# cpu_board.net
KiCad netlist of a schematic drawn in Altium Designer
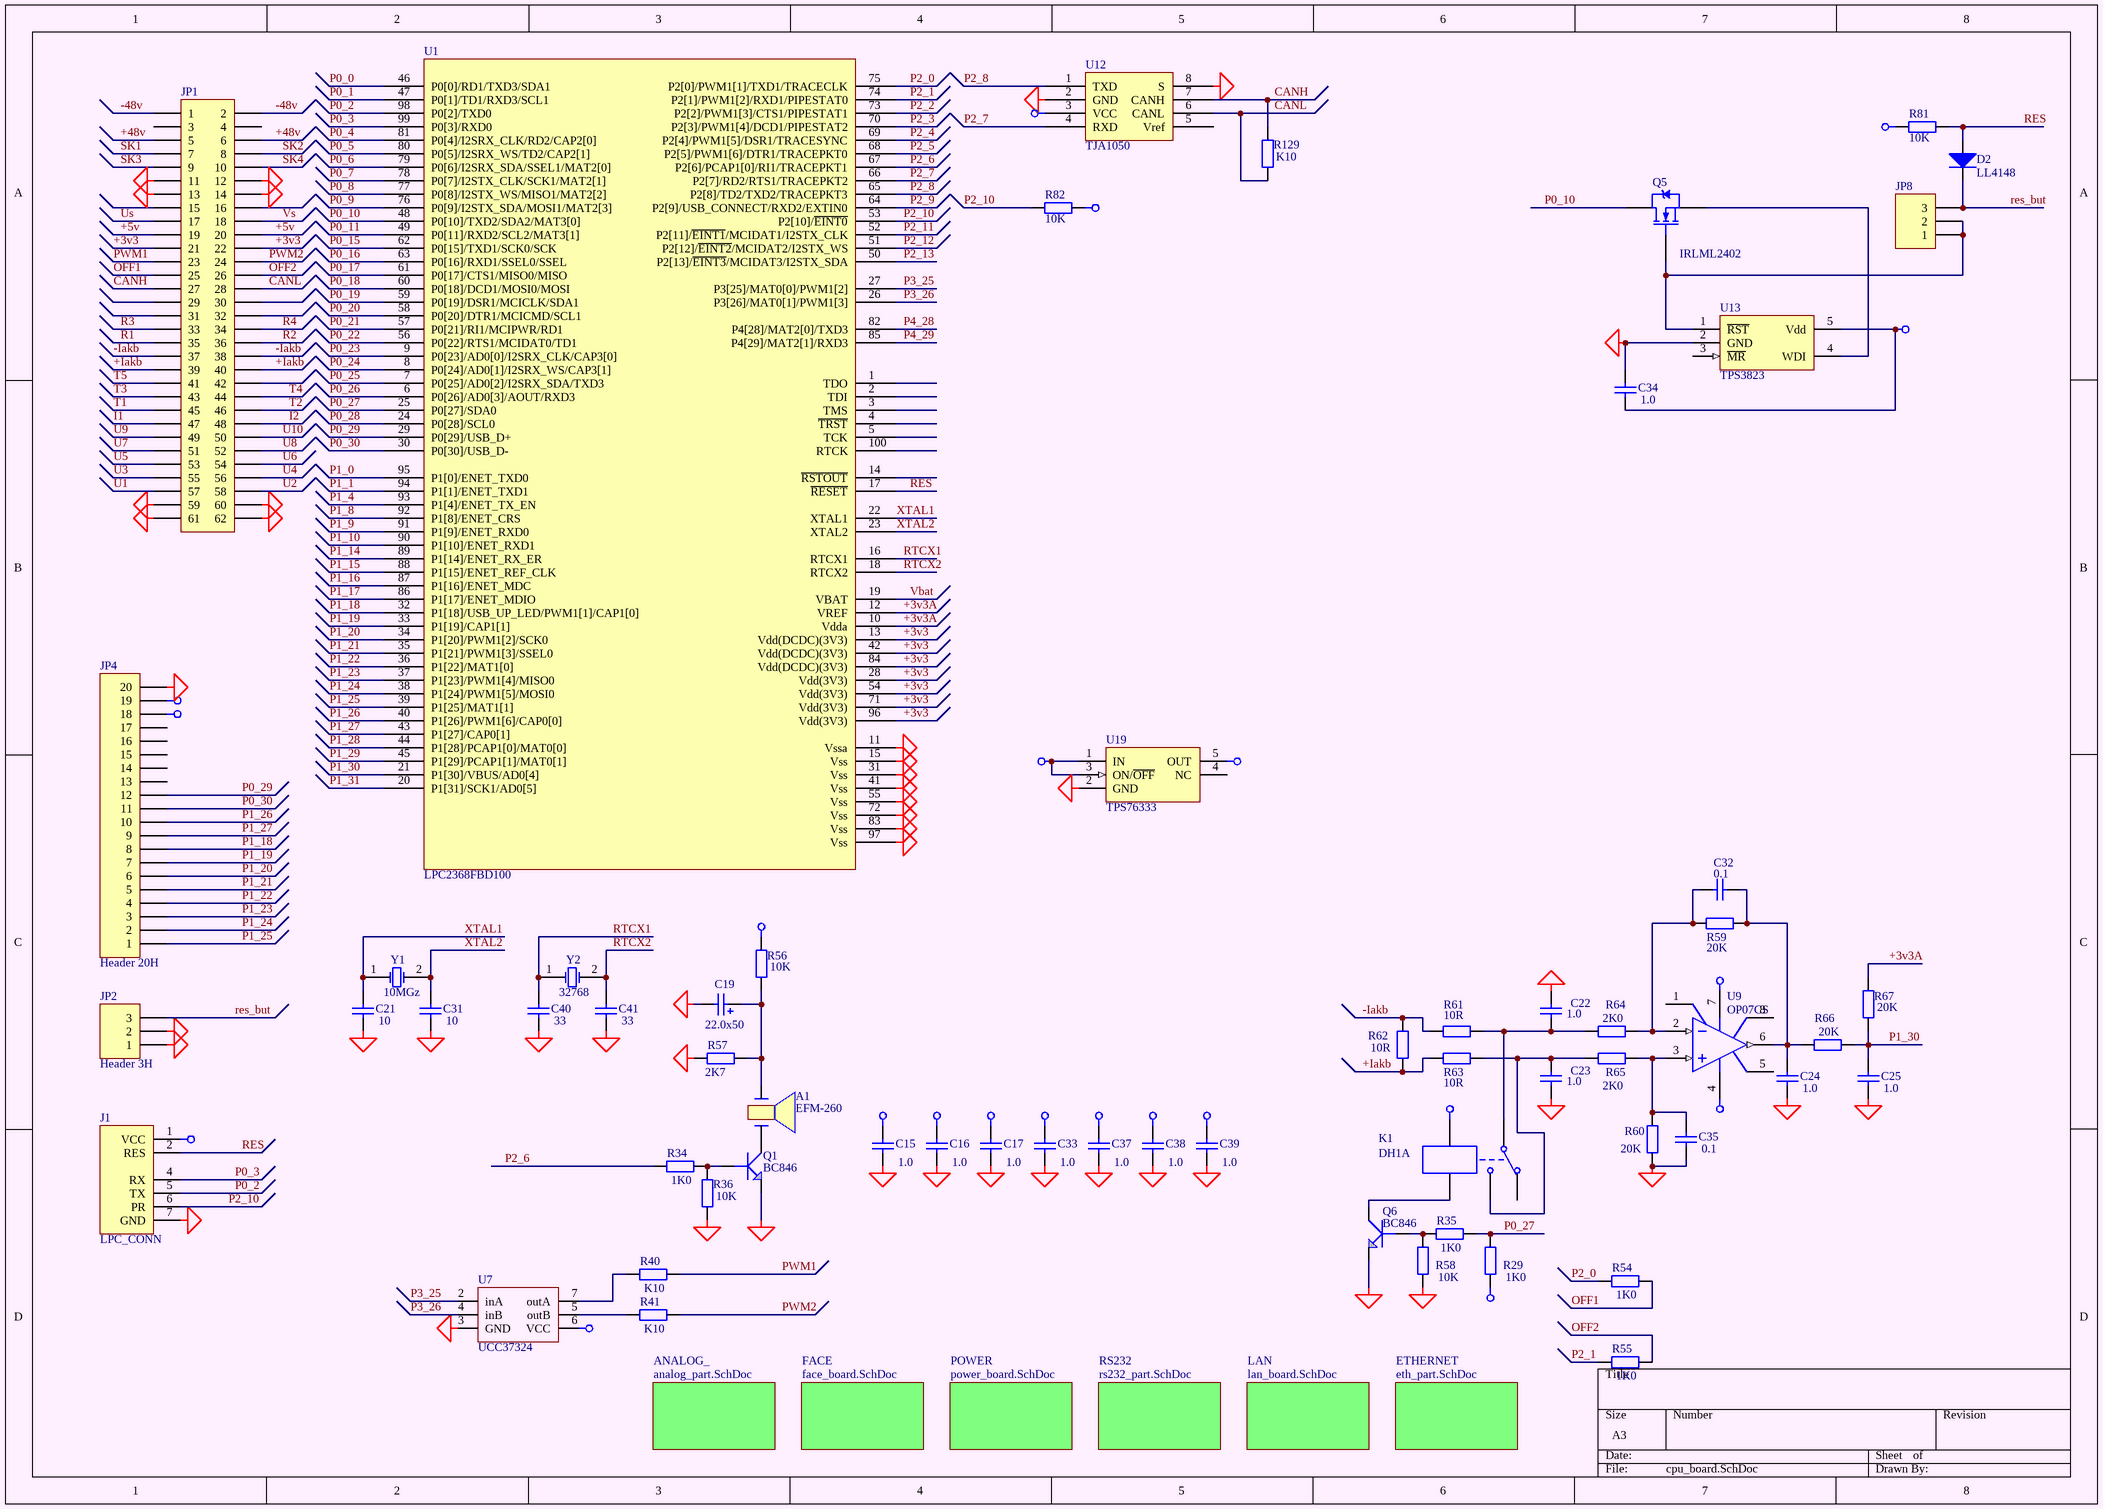
[diagram p0: cpu_board.SchDoc]

(export (version "E")
  (design (tool "Eeschema 10.0.6"))
  (components
    (comp (ref "A1") (value "EFM-260") (footprint "Pjezo15") (libsource (lib "PAL") (part "PJEZ0")))
    (comp (ref "C15")
      (value "1.0")
      (footprint "C3216-1206")
      (description "Capacitor (Semiconductor SIM Model)")
      (fields (field (name "MANUFACTURER") "Generic Components") (field (name "PUBLISHER") "Altium Limited"))
      (libsource (lib "Miscellaneous Devices") (part "Cap Semi"))
    )
    (comp (ref "C16")
      (value "1.0")
      (footprint "C3216-1206")
      (description "Capacitor (Semiconductor SIM Model)")
      (fields (field (name "MANUFACTURER") "Generic Components") (field (name "PUBLISHER") "Altium Limited"))
      (libsource (lib "Miscellaneous Devices") (part "Cap Semi"))
    )
    (comp (ref "C17")
      (value "1.0")
      (footprint "_1206")
      (description "Capacitor (Semiconductor SIM Model)")
      (fields (field (name "MANUFACTURER") "Generic Components") (field (name "PUBLISHER") "Altium Limited"))
      (libsource (lib "Miscellaneous Devices") (part "Cap Semi"))
    )
    (comp (ref "C19")
      (value "22.0x50")
      (footprint "el3")
      (description "Polarized Capacitor (Radial)")
      (fields (field (name "MANUFACTURER") "Generic Components") (field (name "PUBLISHER") "Altium Limited"))
      (libsource (lib "PAL") (part "Cap Pol1"))
    )
    (comp (ref "C21")
      (value "10")
      (footprint "_1206")
      (description "Capacitor (Semiconductor SIM Model)")
      (fields (field (name "MANUFACTURER") "Generic Components") (field (name "PUBLISHER") "Altium Limited"))
      (libsource (lib "Miscellaneous Devices") (part "Cap Semi"))
    )
    (comp (ref "C22")
      (value "1.0")
      (footprint "_1206")
      (description "Capacitor (Semiconductor SIM Model)")
      (fields (field (name "MANUFACTURER") "Generic Components") (field (name "PUBLISHER") "Altium Limited"))
      (libsource (lib "Miscellaneous Devices") (part "Cap Semi"))
    )
    (comp (ref "C23")
      (value "1.0")
      (footprint "_1206")
      (description "Capacitor (Semiconductor SIM Model)")
      (fields (field (name "MANUFACTURER") "Generic Components") (field (name "PUBLISHER") "Altium Limited"))
      (libsource (lib "Miscellaneous Devices") (part "Cap Semi"))
    )
    (comp (ref "C24")
      (value "1.0")
      (footprint "_1206")
      (description "Capacitor (Semiconductor SIM Model)")
      (fields (field (name "MANUFACTURER") "Generic Components") (field (name "PUBLISHER") "Altium Limited"))
      (libsource (lib "Miscellaneous Devices") (part "Cap Semi"))
    )
    (comp (ref "C25")
      (value "1.0")
      (footprint "_1206")
      (description "Capacitor (Semiconductor SIM Model)")
      (fields (field (name "MANUFACTURER") "Generic Components") (field (name "PUBLISHER") "Altium Limited"))
      (libsource (lib "Miscellaneous Devices") (part "Cap Semi"))
    )
    (comp (ref "C31")
      (value "10")
      (footprint "_1206")
      (description "Capacitor (Semiconductor SIM Model)")
      (fields (field (name "MANUFACTURER") "Generic Components") (field (name "PUBLISHER") "Altium Limited"))
      (libsource (lib "Miscellaneous Devices") (part "Cap Semi"))
    )
    (comp (ref "C32")
      (value "0.1")
      (footprint "_1206")
      (description "Capacitor (Semiconductor SIM Model)")
      (fields (field (name "MANUFACTURER") "Generic Components") (field (name "PUBLISHER") "Altium Limited"))
      (libsource (lib "Miscellaneous Devices") (part "Cap Semi"))
    )
    (comp (ref "C33")
      (value "1.0")
      (footprint "_1206")
      (description "Capacitor (Semiconductor SIM Model)")
      (fields (field (name "MANUFACTURER") "Generic Components") (field (name "PUBLISHER") "Altium Limited"))
      (libsource (lib "Miscellaneous Devices") (part "Cap Semi"))
    )
    (comp (ref "C34")
      (value "1.0")
      (footprint "_1206")
      (description "Capacitor")
      (fields (field (name "MANUFACTURER") "Generic Components") (field (name "PUBLISHER") "Altium Limited"))
      (libsource (lib "Miscellaneous Devices") (part "Cap Semi"))
    )
    (comp (ref "C35")
      (value "0.1")
      (footprint "_1206")
      (description "Capacitor (Semiconductor SIM Model)")
      (fields (field (name "MANUFACTURER") "Generic Components") (field (name "PUBLISHER") "Altium Limited"))
      (libsource (lib "Miscellaneous Devices") (part "Cap Semi"))
    )
    (comp (ref "C37")
      (value "1.0")
      (footprint "_1206")
      (description "Capacitor (Semiconductor SIM Model)")
      (fields (field (name "MANUFACTURER") "Generic Components") (field (name "PUBLISHER") "Altium Limited"))
      (libsource (lib "Miscellaneous Devices") (part "Cap Semi"))
    )
    (comp (ref "C38")
      (value "1.0")
      (footprint "_1206")
      (description "Capacitor (Semiconductor SIM Model)")
      (fields (field (name "MANUFACTURER") "Generic Components") (field (name "PUBLISHER") "Altium Limited"))
      (libsource (lib "Miscellaneous Devices") (part "Cap Semi"))
    )
    (comp (ref "C39")
      (value "1.0")
      (footprint "_1206")
      (description "Capacitor (Semiconductor SIM Model)")
      (fields (field (name "MANUFACTURER") "Generic Components") (field (name "PUBLISHER") "Altium Limited"))
      (libsource (lib "Miscellaneous Devices") (part "Cap Semi"))
    )
    (comp (ref "C40")
      (value "33")
      (footprint "_1206")
      (description "Capacitor (Semiconductor SIM Model)")
      (fields (field (name "MANUFACTURER") "Generic Components") (field (name "PUBLISHER") "Altium Limited"))
      (libsource (lib "Miscellaneous Devices") (part "Cap Semi"))
    )
    (comp (ref "C41")
      (value "33")
      (footprint "_1206")
      (description "Capacitor (Semiconductor SIM Model)")
      (fields (field (name "MANUFACTURER") "Generic Components") (field (name "PUBLISHER") "Altium Limited"))
      (libsource (lib "Miscellaneous Devices") (part "Cap Semi"))
    )
    (comp (ref "D2")
      (value "LL4148")
      (footprint "_1206d")
      (description "Default Diode")
      (fields (field (name "MANUFACTURER") "Generic Components") (field (name "PUBLISHER") "Altium Limited"))
      (libsource (lib "PAL") (part "Diode"))
    )
    (comp (ref "J1") (value "LPC_CONN") (footprint "HDR1X7") (libsource (lib "PAL") (part "LPC_CONN")))
    (comp (ref "JP1")
      (value "~")
      (footprint "HDR2X30")
      (description "Header, 30-Pin, Dual row")
      (fields (field (name "MANUFACTURER") "Generic Components") (field (name "PUBLISHER") "Altium Limited"))
      (libsource (lib "UKU205") (part "Header 31X2"))
    )
    (comp (ref "JP2")
      (value "Header 3H")
      (footprint "HDR1X3H")
      (description "Header, 3-Pin,  Right Angle")
      (fields (field (name "MANUFACTURER") "Generic Components") (field (name "PUBLISHER") "Altium Limited"))
      (libsource (lib "Miscellaneous Connectors") (part "Header 3H"))
    )
    (comp (ref "JP4")
      (value "Header 20H")
      (footprint "HDR1X20H")
      (description "Header, 20-Pin,  Right Angle")
      (fields (field (name "MANUFACTURER") "Generic Components") (field (name "PUBLISHER") "Altium Limited"))
      (libsource (lib "Miscellaneous Connectors") (part "Header 20H"))
    )
    (comp (ref "JP8")
      (value "PLS-3")
      (footprint "HDR1X3")
      (description "Header, 3-Pin")
      (fields (field (name "MANUFACTURER") "Generic Components") (field (name "PUBLISHER") "Altium Limited"))
      (libsource (lib "Miscellaneous Connectors") (part "Header 3"))
    )
    (comp (ref "K1")
      (value "DH1A")
      (footprint "kuan")
      (description "Single-Pole Dual-Throw Relay")
      (fields (field (name "MANUFACTURER") "Generic Components") (field (name "PUBLISHER") "Altium Limited"))
      (libsource (lib "PAL") (part "BS115"))
    )
    (comp (ref "Q1") (value "BC846") (footprint "SO-G3") (libsource (lib "MAIN") (part "GT122")))
    (comp (ref "Q5")
      (value "IRLML2402")
      (footprint "SO-G3")
      (description "HEXFET Power MOSFET")
      (fields
        (field (name "MANUFACTURER") "International Rectifier")
        (field (name "ALTIUM_VALUE") "IRLML2402")
        (field (name "PUBLISHER") "Altium Limited")
      )
      (libsource (lib "IR Discrete MOSFET") (part "IRLML2402"))
    )
    (comp (ref "Q6") (value "BC846") (footprint "SO-G3") (libsource (lib "MAIN") (part "GT122")))
    (comp (ref "R29")
      (value "1K0")
      (footprint "_1206")
      (description "Resistor")
      (fields (field (name "MANUFACTURER") "Generic Components") (field (name "PUBLISHER") "Altium Limited"))
      (libsource (lib "") (part "Res2_2"))
    )
    (comp (ref "R34")
      (value "1K0")
      (footprint "_1206")
      (description "Resistor")
      (fields (field (name "MANUFACTURER") "Generic Components") (field (name "PUBLISHER") "Altium Limited"))
      (libsource (lib "") (part "Res2_2"))
    )
    (comp (ref "R35")
      (value "1K0")
      (footprint "_1206")
      (description "Resistor")
      (fields (field (name "MANUFACTURER") "Generic Components") (field (name "PUBLISHER") "Altium Limited"))
      (libsource (lib "") (part "Res2_3"))
    )
    (comp (ref "R36")
      (value "10K")
      (footprint "_1206")
      (description "Resistor")
      (fields (field (name "MANUFACTURER") "Generic Components") (field (name "PUBLISHER") "Altium Limited"))
      (libsource (lib "") (part "Res2_1"))
    )
    (comp (ref "R40")
      (value "K10")
      (footprint "_1206")
      (description "Resistor")
      (fields (field (name "MANUFACTURER") "Generic Components") (field (name "PUBLISHER") "Altium Limited"))
      (libsource (lib "Miscellaneous Devices") (part "Res2"))
    )
    (comp (ref "R41")
      (value "K10")
      (footprint "_1206")
      (description "Resistor")
      (fields (field (name "MANUFACTURER") "Generic Components") (field (name "PUBLISHER") "Altium Limited"))
      (libsource (lib "Miscellaneous Devices") (part "Res2"))
    )
    (comp (ref "R54")
      (value "1K0")
      (footprint "_1206")
      (description "Resistor")
      (fields (field (name "MANUFACTURER") "Generic Components") (field (name "PUBLISHER") "Altium Limited"))
      (libsource (lib "") (part "Res2_2"))
    )
    (comp (ref "R55")
      (value "1K0")
      (footprint "_1206")
      (description "Resistor")
      (fields (field (name "MANUFACTURER") "Generic Components") (field (name "PUBLISHER") "Altium Limited"))
      (libsource (lib "") (part "Res2_2"))
    )
    (comp (ref "R56")
      (value "10K")
      (footprint "_1206")
      (description "Resistor")
      (fields (field (name "MANUFACTURER") "Generic Components") (field (name "PUBLISHER") "Altium Limited"))
      (libsource (lib "") (part "Res2_1"))
    )
    (comp (ref "R57")
      (value "2K7")
      (footprint "_1206")
      (description "Resistor")
      (fields (field (name "MANUFACTURER") "Generic Components") (field (name "PUBLISHER") "Altium Limited"))
      (libsource (lib "") (part "Res2_2"))
    )
    (comp (ref "R58")
      (value "10K")
      (footprint "_1206")
      (description "Resistor")
      (fields (field (name "MANUFACTURER") "Generic Components") (field (name "PUBLISHER") "Altium Limited"))
      (libsource (lib "") (part "Res2_2"))
    )
    (comp (ref "R59")
      (value "20K")
      (footprint "_1206")
      (description "Resistor")
      (fields (field (name "MANUFACTURER") "Generic Components") (field (name "PUBLISHER") "Altium Limited"))
      (libsource (lib "Miscellaneous Devices") (part "Res2"))
    )
    (comp (ref "R60")
      (value "20K")
      (footprint "_1206")
      (description "Resistor")
      (fields (field (name "MANUFACTURER") "Generic Components") (field (name "PUBLISHER") "Altium Limited"))
      (libsource (lib "") (part "Res2_1"))
    )
    (comp (ref "R61")
      (value "10R")
      (footprint "_1206")
      (description "Resistor")
      (fields (field (name "MANUFACTURER") "Generic Components") (field (name "PUBLISHER") "Altium Limited"))
      (libsource (lib "Miscellaneous Devices") (part "Res2"))
    )
    (comp (ref "R62")
      (value "10R")
      (footprint "_1206")
      (description "Resistor")
      (fields (field (name "MANUFACTURER") "Generic Components") (field (name "PUBLISHER") "Altium Limited"))
      (libsource (lib "") (part "Res2_1"))
    )
    (comp (ref "R63")
      (value "10R")
      (footprint "_1206")
      (description "Resistor")
      (fields (field (name "MANUFACTURER") "Generic Components") (field (name "PUBLISHER") "Altium Limited"))
      (libsource (lib "Miscellaneous Devices") (part "Res2"))
    )
    (comp (ref "R64")
      (value "2K0")
      (footprint "_1206")
      (description "Resistor")
      (fields (field (name "MANUFACTURER") "Generic Components") (field (name "PUBLISHER") "Altium Limited"))
      (libsource (lib "") (part "Res2_2"))
    )
    (comp (ref "R65")
      (value "2K0")
      (footprint "_1206")
      (description "Resistor")
      (fields (field (name "MANUFACTURER") "Generic Components") (field (name "PUBLISHER") "Altium Limited"))
      (libsource (lib "") (part "Res2_2"))
    )
    (comp (ref "R66")
      (value "20K")
      (footprint "_1206")
      (description "Resistor")
      (fields (field (name "MANUFACTURER") "Generic Components") (field (name "PUBLISHER") "Altium Limited"))
      (libsource (lib "") (part "Res2_2"))
    )
    (comp (ref "R67")
      (value "20K")
      (footprint "_1206")
      (description "Resistor")
      (fields (field (name "MANUFACTURER") "Generic Components") (field (name "PUBLISHER") "Altium Limited"))
      (libsource (lib "") (part "Res2_2"))
    )
    (comp (ref "R81")
      (value "10K")
      (footprint "_1206")
      (description "Resistor")
      (fields (field (name "MANUFACTURER") "Generic Components") (field (name "PUBLISHER") "Altium Limited"))
      (libsource (lib "Miscellaneous Devices") (part "Res2"))
    )
    (comp (ref "R82")
      (value "10K")
      (footprint "_1206")
      (description "Resistor")
      (fields (field (name "MANUFACTURER") "Generic Components") (field (name "PUBLISHER") "Altium Limited"))
      (libsource (lib "Miscellaneous Devices") (part "Res2"))
    )
    (comp (ref "R129")
      (value "K10")
      (footprint "_1206")
      (description "Resistor")
      (fields (field (name "MANUFACTURER") "Generic Components") (field (name "PUBLISHER") "Altium Limited"))
      (libsource (lib "") (part "Res2_1"))
    )
    (comp (ref "U1")
      (value "LPC2368FBD100")
      (footprint "LPC2368")
      (libsource (lib "PAL") (part "LPC2368FBD100"))
    )
    (comp (ref "U7") (value "UCC37324") (footprint "SO-G8") (libsource (lib "PAL") (part "UCC37324")))
    (comp (ref "U9")
      (value "OP07CS")
      (footprint "SO-G8")
      (description "Ultra-Low Offset Voltage Operational Amplifier")
      (fields (field (name "MANUFACTURER") "Analog Devices") (field (name "PUBLISHER") "Altium Limited"))
      (libsource (lib "AD Operational Amplifier") (part "OP07CS"))
    )
    (comp (ref "U12") (value "TJA1050") (footprint "SO-G8") (libsource (lib "PAL") (part "TJA1050")))
    (comp (ref "U13")
      (value "TPS3823")
      (footprint "SO-G5/P.95")
      (description "Reset IC")
      (fields
        (field (name "MANUFACTURER") "National Semiconductor")
        (field (name "PUBLISHER") "Altium Limited")
      )
      (libsource (lib "PAL") (part "TPS3823"))
    )
    (comp (ref "U19")
      (value "TPS76333")
      (footprint "SO-G5/P.95")
      (description "Micropower SOT, 50 mA Ultra Low-Dropout Regulator")
      (fields
        (field (name "MANUFACTURER") "National Semiconductor")
        (field (name "PUBLISHER") "Altium Limited")
      )
      (libsource (lib "NSC Power Mgt Voltage Regulator") (part "LP2980AIM5-3.3"))
    )
    (comp (ref "Y1")
      (value "10MGz")
      (footprint "QWARZ1")
      (description "Crystal Oscillator")
      (fields (field (name "MANUFACTURER") "Generic Components") (field (name "PUBLISHER") "Altium Limited"))
      (libsource (lib "") (part "XTAL_1"))
    )
    (comp (ref "Y2")
      (value "32768")
      (footprint "QWARZ2")
      (description "Crystal Oscillator")
      (fields (field (name "MANUFACTURER") "Generic Components") (field (name "PUBLISHER") "Altium Limited"))
      (libsource (lib "Miscellaneous Devices") (part "XTAL"))
    )
  )
  (nets
    (net (code "1") (name "+3v3") (class "Default")
      (node (ref "C34") (pin "1") (pinfunction "1_1") (pintype "passive"))
      (node (ref "C37") (pin "2") (pinfunction "2_2") (pintype "passive"))
      (node (ref "C38") (pin "2") (pinfunction "2_2") (pintype "passive"))
      (node (ref "C39") (pin "2") (pinfunction "2_2") (pintype "passive"))
      (node (ref "J1") (pin "1") (pinfunction "VCC_1") (pintype "passive"))
      (node (ref "JP1") (pin "21") (pinfunction "21_21") (pintype "passive"))
      (node (ref "JP1") (pin "22") (pinfunction "22_22") (pintype "passive"))
      (node (ref "R81") (pin "2") (pinfunction "2_2") (pintype "passive"))
      (node (ref "R82") (pin "1") (pinfunction "1_1") (pintype "passive"))
      (node (ref "U1") (pin "13") (pinfunction "Vdd(DCDC)(3V3)_13") (pintype "passive"))
      (node (ref "U1") (pin "28") (pinfunction "Vdd(3V3)_28") (pintype "passive"))
      (node (ref "U1") (pin "42") (pinfunction "Vdd(DCDC)(3V3)_42") (pintype "passive"))
      (node (ref "U1") (pin "54") (pinfunction "Vdd(3V3)_54") (pintype "passive"))
      (node (ref "U1") (pin "71") (pinfunction "Vdd(3V3)_71") (pintype "passive"))
      (node (ref "U1") (pin "84") (pinfunction "Vdd(DCDC)(3V3)_84") (pintype "passive"))
      (node (ref "U1") (pin "96") (pinfunction "Vdd(3V3)_96") (pintype "passive"))
      (node (ref "U13") (pin "5") (pinfunction "Vdd_5") (pintype "power_in"))
    )
    (net (code "2") (name "+3v3A") (class "Default")
      (node (ref "C17") (pin "2") (pinfunction "2_2") (pintype "passive"))
      (node (ref "C33") (pin "2") (pinfunction "2_2") (pintype "passive"))
      (node (ref "R67") (pin "2") (pinfunction "2_2") (pintype "passive"))
      (node (ref "U1") (pin "10") (pinfunction "Vdda_10") (pintype "passive"))
      (node (ref "U1") (pin "12") (pinfunction "VREF_12") (pintype "passive"))
      (node (ref "U19") (pin "5") (pinfunction "OUT_5") (pintype "power_in"))
    )
    (net (code "3") (name "+5v") (class "Default")
      (node (ref "C15") (pin "2") (pinfunction "2_2") (pintype "passive"))
      (node (ref "JP1") (pin "19") (pinfunction "19_19") (pintype "passive"))
      (node (ref "JP1") (pin "20") (pinfunction "20_20") (pintype "passive"))
      (node (ref "JP4") (pin "19") (pinfunction "19_19") (pintype "passive"))
      (node (ref "K1") (pin "4") (pinfunction "4_4") (pintype "passive"))
      (node (ref "R29") (pin "1") (pinfunction "1_1") (pintype "passive"))
      (node (ref "U12") (pin "3") (pinfunction "VCC_3") (pintype "passive"))
      (node (ref "U19") (pin "1") (pinfunction "IN_1") (pintype "power_in"))
      (node (ref "U19") (pin "3") (pinfunction "ON/~{OFF}_3") (pintype "input"))
      (node (ref "U7") (pin "6") (pinfunction "VCC_6") (pintype "passive"))
      (node (ref "U9") (pin "7") (pinfunction "V+_7") (pintype "power_in"))
    )
    (net (code "4") (name "+48v") (class "Default")
      (node (ref "JP1") (pin "5") (pinfunction "5_5") (pintype "passive"))
      (node (ref "JP1") (pin "6") (pinfunction "6_6") (pintype "passive"))
      (node (ref "R56") (pin "2") (pinfunction "2_2") (pintype "passive"))
    )
    (net (code "5") (name "-5v") (class "Default")
      (node (ref "C16") (pin "2") (pinfunction "2_2") (pintype "passive"))
      (node (ref "JP4") (pin "18") (pinfunction "18_18") (pintype "passive"))
      (node (ref "U9") (pin "4") (pinfunction "V-_4") (pintype "power_in"))
    )
    (net (code "6") (name "/+Iakb") (class "Default")
      (node (ref "JP1") (pin "39") (pinfunction "39_39") (pintype "passive"))
      (node (ref "JP1") (pin "40") (pinfunction "40_40") (pintype "passive"))
      (node (ref "R62") (pin "1") (pinfunction "1_1") (pintype "passive"))
      (node (ref "R63") (pin "2") (pinfunction "2_2") (pintype "passive"))
    )
    (net (code "7") (name "/-48v") (class "Default")
      (node (ref "JP1") (pin "1") (pinfunction "1_1") (pintype "passive"))
      (node (ref "JP1") (pin "2") (pinfunction "2_2") (pintype "passive"))
    )
    (net (code "8") (name "/-Iakb") (class "Default")
      (node (ref "JP1") (pin "37") (pinfunction "37_37") (pintype "passive"))
      (node (ref "JP1") (pin "38") (pinfunction "38_38") (pintype "passive"))
      (node (ref "R61") (pin "2") (pinfunction "2_2") (pintype "passive"))
      (node (ref "R62") (pin "2") (pinfunction "2_2") (pintype "passive"))
    )
    (net (code "10") (name "/CANH") (class "Default")
      (node (ref "JP1") (pin "27") (pinfunction "27_27") (pintype "passive"))
      (node (ref "R129") (pin "2") (pinfunction "2_2") (pintype "passive"))
      (node (ref "U12") (pin "7") (pinfunction "CANH_7") (pintype "passive"))
    )
    (net (code "11") (name "/CANL") (class "Default")
      (node (ref "JP1") (pin "28") (pinfunction "28_28") (pintype "passive"))
      (node (ref "R129") (pin "1") (pinfunction "1_1") (pintype "passive"))
      (node (ref "U12") (pin "6") (pinfunction "CANL_6") (pintype "passive"))
    )
    (net (code "12") (name "/I1") (class "Default")
      (node (ref "JP1") (pin "47") (pinfunction "47_47") (pintype "passive"))
    )
    (net (code "13") (name "/I2") (class "Default")
      (node (ref "JP1") (pin "48") (pinfunction "48_48") (pintype "passive"))
    )
    (net (code "14") (name "/OFF1") (class "Default")
      (node (ref "JP1") (pin "25") (pinfunction "25_25") (pintype "passive"))
      (node (ref "R54") (pin "2") (pinfunction "2_2") (pintype "passive"))
    )
    (net (code "15") (name "/OFF2") (class "Default")
      (node (ref "JP1") (pin "26") (pinfunction "26_26") (pintype "passive"))
      (node (ref "R55") (pin "2") (pinfunction "2_2") (pintype "passive"))
    )
    (net (code "16") (name "/P0_0") (class "Default")
      (node (ref "U1") (pin "46") (pinfunction "P0[0]/RD1/TXD3/SDA1_46") (pintype "passive"))
    )
    (net (code "17") (name "/P0_1") (class "Default")
      (node (ref "U1") (pin "47") (pinfunction "P0[1]/TD1/RXD3/SCL1_47") (pintype "passive"))
    )
    (net (code "18") (name "/P0_2") (class "Default")
      (node (ref "J1") (pin "5") (pinfunction "TX_5") (pintype "passive"))
      (node (ref "U1") (pin "98") (pinfunction "P0[2]/TXD0_98") (pintype "passive"))
    )
    (net (code "19") (name "/P0_3") (class "Default")
      (node (ref "J1") (pin "4") (pinfunction "RX_4") (pintype "passive"))
      (node (ref "U1") (pin "99") (pinfunction "P0[3]/RXD0_99") (pintype "passive"))
    )
    (net (code "20") (name "/P0_4") (class "Default")
      (node (ref "U1") (pin "81") (pinfunction "P0[4]/I2SRX_CLK/RD2/CAP2[0]_81") (pintype "passive"))
    )
    (net (code "21") (name "/P0_5") (class "Default")
      (node (ref "U1") (pin "80") (pinfunction "P0[5]/I2SRX_WS/TD2/CAP2[1]_80") (pintype "passive"))
    )
    (net (code "22") (name "/P0_6") (class "Default")
      (node (ref "U1") (pin "79") (pinfunction "P0[6]/I2SRX_SDA/SSEL1/MAT2[0]_79") (pintype "passive"))
    )
    (net (code "23") (name "/P0_7") (class "Default")
      (node (ref "U1") (pin "78") (pinfunction "P0[7]/I2STX_CLK/SCK1/MAT2[1]_78") (pintype "passive"))
    )
    (net (code "24") (name "/P0_8") (class "Default")
      (node (ref "U1") (pin "77") (pinfunction "P0[8]/I2STX_WS/MISO1/MAT2[2]_77") (pintype "passive"))
    )
    (net (code "25") (name "/P0_9") (class "Default")
      (node (ref "U1") (pin "76") (pinfunction "P0[9]/I2STX_SDA/MOSI1/MAT2[3]_76") (pintype "passive"))
    )
    (net (code "26") (name "/P0_10") (class "Default")
      (node (ref "Q5") (pin "3") (pinfunction "D_3") (pintype "passive"))
      (node (ref "U1") (pin "48") (pinfunction "P0[10]/TXD2/SDA2/MAT3[0]_48") (pintype "passive"))
    )
    (net (code "27") (name "/P0_11") (class "Default")
      (node (ref "U1") (pin "49") (pinfunction "P0[11]/RXD2/SCL2/MAT3[1]_49") (pintype "passive"))
    )
    (net (code "28") (name "/P0_15") (class "Default")
      (node (ref "U1") (pin "62") (pinfunction "P0[15]/TXD1/SCK0/SCK_62") (pintype "passive"))
    )
    (net (code "29") (name "/P0_16") (class "Default")
      (node (ref "U1") (pin "63") (pinfunction "P0[16]/RXD1/SSEL0/SSEL_63") (pintype "passive"))
    )
    (net (code "30") (name "/P0_17") (class "Default")
      (node (ref "U1") (pin "61") (pinfunction "P0[17]/CTS1/MISO0/MISO_61") (pintype "passive"))
    )
    (net (code "31") (name "/P0_18") (class "Default")
      (node (ref "U1") (pin "60") (pinfunction "P0[18]/DCD1/MOSI0/MOSI_60") (pintype "passive"))
    )
    (net (code "32") (name "/P0_19") (class "Default")
      (node (ref "U1") (pin "59") (pinfunction "P0[19]/DSR1/MCICLK/SDA1_59") (pintype "passive"))
    )
    (net (code "33") (name "/P0_20") (class "Default")
      (node (ref "U1") (pin "58") (pinfunction "P0[20]/DTR1/MCICMD/SCL1_58") (pintype "passive"))
    )
    (net (code "34") (name "/P0_21") (class "Default")
      (node (ref "U1") (pin "57") (pinfunction "P0[21]/RI1/MCIPWR/RD1_57") (pintype "passive"))
    )
    (net (code "35") (name "/P0_22") (class "Default")
      (node (ref "U1") (pin "56") (pinfunction "P0[22]/RTS1/MCIDAT0/TD1_56") (pintype "passive"))
    )
    (net (code "36") (name "/P0_23") (class "Default")
      (node (ref "U1") (pin "9") (pinfunction "P0[23]/AD0[0]/I2SRX_CLK/CAP3[0]_9") (pintype "passive"))
    )
    (net (code "37") (name "/P0_24") (class "Default")
      (node (ref "U1") (pin "8") (pinfunction "P0[24]/AD0[1]/I2SRX_WS/CAP3[1]_8") (pintype "passive"))
    )
    (net (code "38") (name "/P0_25") (class "Default")
      (node (ref "U1") (pin "7") (pinfunction "P0[25]/AD0[2]/I2SRX_SDA/TXD3_7") (pintype "passive"))
    )
    (net (code "39") (name "/P0_26") (class "Default")
      (node (ref "U1") (pin "6") (pinfunction "P0[26]/AD0[3]/AOUT/RXD3_6") (pintype "passive"))
    )
    (net (code "40") (name "/P0_27") (class "Default")
      (node (ref "R29") (pin "2") (pinfunction "2_2") (pintype "passive"))
      (node (ref "R35") (pin "1") (pinfunction "1_1") (pintype "passive"))
      (node (ref "U1") (pin "25") (pinfunction "P0[27]/SDA0_25") (pintype "passive"))
    )
    (net (code "41") (name "/P0_28") (class "Default")
      (node (ref "U1") (pin "24") (pinfunction "P0[28]/SCL0_24") (pintype "passive"))
    )
    (net (code "42") (name "/P0_29") (class "Default")
      (node (ref "JP4") (pin "12") (pinfunction "12_12") (pintype "passive"))
      (node (ref "U1") (pin "29") (pinfunction "P0[29]/USB_D+_29") (pintype "passive"))
    )
    (net (code "43") (name "/P0_30") (class "Default")
      (node (ref "JP4") (pin "11") (pinfunction "11_11") (pintype "passive"))
      (node (ref "U1") (pin "30") (pinfunction "P0[30]/USB_D-_30") (pintype "passive"))
    )
    (net (code "44") (name "/P1_0") (class "Default")
      (node (ref "U1") (pin "95") (pinfunction "P1[0]/ENET_TXD0_95") (pintype "passive"))
    )
    (net (code "45") (name "/P1_1") (class "Default")
      (node (ref "U1") (pin "94") (pinfunction "P1[1]/ENET_TXD1_94") (pintype "passive"))
    )
    (net (code "46") (name "/P1_4") (class "Default")
      (node (ref "U1") (pin "93") (pinfunction "P1[4]/ENET_TX_EN_93") (pintype "passive"))
    )
    (net (code "47") (name "/P1_8") (class "Default")
      (node (ref "U1") (pin "92") (pinfunction "P1[8]/ENET_CRS_92") (pintype "passive"))
    )
    (net (code "48") (name "/P1_9") (class "Default")
      (node (ref "U1") (pin "91") (pinfunction "P1[9]/ENET_RXD0_91") (pintype "passive"))
    )
    (net (code "49") (name "/P1_10") (class "Default")
      (node (ref "U1") (pin "90") (pinfunction "P1[10]/ENET_RXD1_90") (pintype "passive"))
    )
    (net (code "50") (name "/P1_14") (class "Default")
      (node (ref "U1") (pin "89") (pinfunction "P1[14]/ENET_RX_ER_89") (pintype "passive"))
    )
    (net (code "51") (name "/P1_15") (class "Default")
      (node (ref "U1") (pin "88") (pinfunction "P1[15]/ENET_REF_CLK_88") (pintype "passive"))
    )
    (net (code "52") (name "/P1_16") (class "Default")
      (node (ref "U1") (pin "87") (pinfunction "P1[16]/ENET_MDC_87") (pintype "passive"))
    )
    (net (code "53") (name "/P1_17") (class "Default")
      (node (ref "U1") (pin "86") (pinfunction "P1[17]/ENET_MDIO_86") (pintype "passive"))
    )
    (net (code "54") (name "/P1_18") (class "Default")
      (node (ref "JP4") (pin "8") (pinfunction "8_8") (pintype "passive"))
      (node (ref "U1") (pin "32") (pinfunction "P1[18]/USB_UP_LED/PWM1[1]/CAP1[0]_32") (pintype "passive"))
    )
    (net (code "55") (name "/P1_19") (class "Default")
      (node (ref "JP4") (pin "7") (pinfunction "7_7") (pintype "passive"))
      (node (ref "U1") (pin "33") (pinfunction "P1[19]/CAP1[1]_33") (pintype "passive"))
    )
    (net (code "56") (name "/P1_20") (class "Default")
      (node (ref "JP4") (pin "6") (pinfunction "6_6") (pintype "passive"))
      (node (ref "U1") (pin "34") (pinfunction "P1[20]/PWM1[2]/SCK0_34") (pintype "passive"))
    )
    (net (code "57") (name "/P1_21") (class "Default")
      (node (ref "JP4") (pin "5") (pinfunction "5_5") (pintype "passive"))
      (node (ref "U1") (pin "35") (pinfunction "P1[21]/PWM1[3]/SSEL0_35") (pintype "passive"))
    )
    (net (code "58") (name "/P1_22") (class "Default")
      (node (ref "JP4") (pin "4") (pinfunction "4_4") (pintype "passive"))
      (node (ref "U1") (pin "36") (pinfunction "P1[22]/MAT1[0]_36") (pintype "passive"))
    )
    (net (code "59") (name "/P1_23") (class "Default")
      (node (ref "JP4") (pin "3") (pinfunction "3_3") (pintype "passive"))
      (node (ref "U1") (pin "37") (pinfunction "P1[23]/PWM1[4]/MISO0_37") (pintype "passive"))
    )
    (net (code "60") (name "/P1_24") (class "Default")
      (node (ref "JP4") (pin "2") (pinfunction "2_2") (pintype "passive"))
      (node (ref "U1") (pin "38") (pinfunction "P1[24]/PWM1[5]/MOSI0_38") (pintype "passive"))
    )
    (net (code "61") (name "/P1_25") (class "Default")
      (node (ref "JP4") (pin "1") (pinfunction "1_1") (pintype "passive"))
      (node (ref "U1") (pin "39") (pinfunction "P1[25]/MAT1[1]_39") (pintype "passive"))
    )
    (net (code "62") (name "/P1_26") (class "Default")
      (node (ref "JP4") (pin "10") (pinfunction "10_10") (pintype "passive"))
      (node (ref "U1") (pin "40") (pinfunction "P1[26]/PWM1[6]/CAP0[0]_40") (pintype "passive"))
    )
    (net (code "63") (name "/P1_27") (class "Default")
      (node (ref "JP4") (pin "9") (pinfunction "9_9") (pintype "passive"))
      (node (ref "U1") (pin "43") (pinfunction "P1[27]/CAP0[1]_43") (pintype "passive"))
    )
    (net (code "64") (name "/P1_28") (class "Default")
      (node (ref "U1") (pin "44") (pinfunction "P1[28]/PCAP1[0]/MAT0[0]_44") (pintype "passive"))
    )
    (net (code "65") (name "/P1_29") (class "Default")
      (node (ref "U1") (pin "45") (pinfunction "P1[29]/PCAP1[1]/MAT0[1]_45") (pintype "passive"))
    )
    (net (code "66") (name "/P1_30") (class "Default")
      (node (ref "C25") (pin "2") (pinfunction "2_2") (pintype "passive"))
      (node (ref "R66") (pin "2") (pinfunction "2_2") (pintype "passive"))
      (node (ref "R67") (pin "1") (pinfunction "1_1") (pintype "passive"))
      (node (ref "U1") (pin "21") (pinfunction "P1[30]/VBUS/AD0[4]_21") (pintype "passive"))
    )
    (net (code "67") (name "/P1_31") (class "Default")
      (node (ref "U1") (pin "20") (pinfunction "P1[31]/SCK1/AD0[5]_20") (pintype "passive"))
    )
    (net (code "68") (name "/P2_0") (class "Default")
      (node (ref "R54") (pin "1") (pinfunction "1_1") (pintype "passive"))
      (node (ref "U1") (pin "75") (pinfunction "P2[0]/PWM1[1]/TXD1/TRACECLK_75") (pintype "passive"))
    )
    (net (code "69") (name "/P2_1") (class "Default")
      (node (ref "R55") (pin "1") (pinfunction "1_1") (pintype "passive"))
      (node (ref "U1") (pin "74") (pinfunction "P2[1]/PWM1[2]/RXD1/PIPESTAT0_74") (pintype "passive"))
    )
    (net (code "70") (name "/P2_2") (class "Default")
      (node (ref "U1") (pin "73") (pinfunction "P2[2]/PWM1[3]/CTS1/PIPESTAT1_73") (pintype "passive"))
    )
    (net (code "71") (name "/P2_3") (class "Default")
      (node (ref "U1") (pin "70") (pinfunction "P2[3]/PWM1[4]/DCD1/PIPESTAT2_70") (pintype "passive"))
    )
    (net (code "72") (name "/P2_4") (class "Default")
      (node (ref "U1") (pin "69") (pinfunction "P2[4]/PWM1[5]/DSR1/TRACESYNC_69") (pintype "passive"))
    )
    (net (code "73") (name "/P2_5") (class "Default")
      (node (ref "U1") (pin "68") (pinfunction "P2[5]/PWM1[6]/DTR1/TRACEPKT0_68") (pintype "passive"))
    )
    (net (code "74") (name "/P2_6") (class "Default")
      (node (ref "R34") (pin "1") (pinfunction "1_1") (pintype "passive"))
      (node (ref "U1") (pin "67") (pinfunction "P2[6]/PCAP1[0]/RI1/TRACEPKT1_67") (pintype "passive"))
    )
    (net (code "75") (name "/P2_7") (class "Default")
      (node (ref "U1") (pin "66") (pinfunction "P2[7]/RD2/RTS1/TRACEPKT2_66") (pintype "passive"))
      (node (ref "U12") (pin "4") (pinfunction "RXD_4") (pintype "passive"))
    )
    (net (code "76") (name "/P2_8") (class "Default")
      (node (ref "U1") (pin "65") (pinfunction "P2[8]/TD2/TXD2/TRACEPKT3_65") (pintype "passive"))
      (node (ref "U12") (pin "1") (pinfunction "TXD_1") (pintype "passive"))
    )
    (net (code "77") (name "/P2_9") (class "Default")
      (node (ref "U1") (pin "64") (pinfunction "P2[9]/USB_CONNECT/RXD2/EXTIN0_64") (pintype "passive"))
    )
    (net (code "78") (name "/P2_10") (class "Default")
      (node (ref "J1") (pin "6") (pinfunction "PR_6") (pintype "passive"))
      (node (ref "R82") (pin "2") (pinfunction "2_2") (pintype "passive"))
      (node (ref "U1") (pin "53") (pinfunction "P2[10]/~{EINT0}_53") (pintype "passive"))
    )
    (net (code "79") (name "/P2_11") (class "Default")
      (node (ref "U1") (pin "52") (pinfunction "P2[11]/~{EINT1}/MCIDAT1/I2STX_CLK_52") (pintype "passive"))
    )
    (net (code "80") (name "/P2_12") (class "Default")
      (node (ref "U1") (pin "51") (pinfunction "P2[12]/~{EINT2}/MCIDAT2/I2STX_WS_51") (pintype "passive"))
    )
    (net (code "81") (name "/P2_13") (class "Default")
      (node (ref "U1") (pin "50") (pinfunction "P2[13]/~{EINT3}/MCIDAT3/I2STX_SDA_50") (pintype "passive"))
    )
    (net (code "82") (name "/P3_25") (class "Default")
      (node (ref "U1") (pin "27") (pinfunction "P3[25]/MAT0[0]/PWM1[2]_27") (pintype "passive"))
      (node (ref "U7") (pin "2") (pinfunction "inA_2") (pintype "passive"))
    )
    (net (code "83") (name "/P3_26") (class "Default")
      (node (ref "U1") (pin "26") (pinfunction "P3[26]/MAT0[1]/PWM1[3]_26") (pintype "passive"))
      (node (ref "U7") (pin "4") (pinfunction "inB_4") (pintype "passive"))
    )
    (net (code "84") (name "/P4_28") (class "Default")
      (node (ref "U1") (pin "82") (pinfunction "P4[28]/MAT2[0]/TXD3_82") (pintype "passive"))
    )
    (net (code "85") (name "/P4_29") (class "Default")
      (node (ref "U1") (pin "85") (pinfunction "P4[29]/MAT2[1]/RXD3_85") (pintype "passive"))
    )
    (net (code "86") (name "/PWM1") (class "Default")
      (node (ref "JP1") (pin "23") (pinfunction "23_23") (pintype "passive"))
      (node (ref "R40") (pin "1") (pinfunction "1_1") (pintype "passive"))
    )
    (net (code "87") (name "/PWM2") (class "Default")
      (node (ref "JP1") (pin "24") (pinfunction "24_24") (pintype "passive"))
      (node (ref "R41") (pin "1") (pinfunction "1_1") (pintype "passive"))
    )
    (net (code "88") (name "/R1") (class "Default")
      (node (ref "JP1") (pin "35") (pinfunction "35_35") (pintype "passive"))
    )
    (net (code "89") (name "/R2") (class "Default")
      (node (ref "JP1") (pin "36") (pinfunction "36_36") (pintype "passive"))
    )
    (net (code "90") (name "/R3") (class "Default")
      (node (ref "JP1") (pin "33") (pinfunction "33_33") (pintype "passive"))
    )
    (net (code "91") (name "/R4") (class "Default")
      (node (ref "JP1") (pin "34") (pinfunction "34_34") (pintype "passive"))
    )
    (net (code "92") (name "/RES") (class "Default")
      (node (ref "D2") (pin "1") (pinfunction "A_1") (pintype "passive"))
      (node (ref "J1") (pin "2") (pinfunction "RES_2") (pintype "passive"))
      (node (ref "R81") (pin "1") (pinfunction "1_1") (pintype "passive"))
      (node (ref "U1") (pin "17") (pinfunction "~{RESET}_17") (pintype "passive"))
    )
    (net (code "93") (name "/RTCX1") (class "Default")
      (node (ref "C40") (pin "2") (pinfunction "2_2") (pintype "passive"))
      (node (ref "U1") (pin "16") (pinfunction "RTCX1_16") (pintype "passive"))
      (node (ref "Y2") (pin "1") (pinfunction "OSC1_1") (pintype "passive"))
    )
    (net (code "94") (name "/RTCX2") (class "Default")
      (node (ref "C41") (pin "2") (pinfunction "2_2") (pintype "passive"))
      (node (ref "U1") (pin "18") (pinfunction "RTCX2_18") (pintype "passive"))
      (node (ref "Y2") (pin "2") (pinfunction "OSC2_2") (pintype "passive"))
    )
    (net (code "95") (name "/SK1") (class "Default")
      (node (ref "JP1") (pin "7") (pinfunction "7_7") (pintype "passive"))
    )
    (net (code "96") (name "/SK2") (class "Default")
      (node (ref "JP1") (pin "8") (pinfunction "8_8") (pintype "passive"))
    )
    (net (code "97") (name "/SK3") (class "Default")
      (node (ref "JP1") (pin "9") (pinfunction "9_9") (pintype "passive"))
    )
    (net (code "98") (name "/SK4") (class "Default")
      (node (ref "JP1") (pin "10") (pinfunction "10_10") (pintype "passive"))
    )
    (net (code "99") (name "/T1") (class "Default")
      (node (ref "JP1") (pin "45") (pinfunction "45_45") (pintype "passive"))
    )
    (net (code "100") (name "/T2") (class "Default")
      (node (ref "JP1") (pin "46") (pinfunction "46_46") (pintype "passive"))
    )
    (net (code "101") (name "/T3") (class "Default")
      (node (ref "JP1") (pin "43") (pinfunction "43_43") (pintype "passive"))
    )
    (net (code "102") (name "/T4") (class "Default")
      (node (ref "JP1") (pin "44") (pinfunction "44_44") (pintype "passive"))
    )
    (net (code "103") (name "/T5") (class "Default")
      (node (ref "JP1") (pin "41") (pinfunction "41_41") (pintype "passive"))
    )
    (net (code "104") (name "/U1") (class "Default")
      (node (ref "JP1") (pin "57") (pinfunction "57_57") (pintype "passive"))
    )
    (net (code "105") (name "/U2") (class "Default")
      (node (ref "JP1") (pin "58") (pinfunction "58_58") (pintype "passive"))
    )
    (net (code "106") (name "/U3") (class "Default")
      (node (ref "JP1") (pin "55") (pinfunction "55_55") (pintype "passive"))
    )
    (net (code "107") (name "/U4") (class "Default")
      (node (ref "JP1") (pin "56") (pinfunction "56_56") (pintype "passive"))
    )
    (net (code "108") (name "/U5") (class "Default")
      (node (ref "JP1") (pin "53") (pinfunction "53_53") (pintype "passive"))
    )
    (net (code "109") (name "/U6") (class "Default")
      (node (ref "JP1") (pin "54") (pinfunction "54_54") (pintype "passive"))
    )
    (net (code "110") (name "/U7") (class "Default")
      (node (ref "JP1") (pin "51") (pinfunction "51_51") (pintype "passive"))
    )
    (net (code "111") (name "/U8") (class "Default")
      (node (ref "JP1") (pin "52") (pinfunction "52_52") (pintype "passive"))
    )
    (net (code "112") (name "/U9") (class "Default")
      (node (ref "JP1") (pin "49") (pinfunction "49_49") (pintype "passive"))
    )
    (net (code "113") (name "/U10") (class "Default")
      (node (ref "JP1") (pin "50") (pinfunction "50_50") (pintype "passive"))
    )
    (net (code "114") (name "/Us") (class "Default")
      (node (ref "JP1") (pin "17") (pinfunction "17_17") (pintype "passive"))
    )
    (net (code "115") (name "/Vbat") (class "Default")
      (node (ref "U1") (pin "19") (pinfunction "VBAT_19") (pintype "passive"))
    )
    (net (code "116") (name "/Vs") (class "Default")
      (node (ref "JP1") (pin "18") (pinfunction "18_18") (pintype "passive"))
    )
    (net (code "117") (name "/XTAL1") (class "Default")
      (node (ref "C21") (pin "2") (pinfunction "2_2") (pintype "passive"))
      (node (ref "U1") (pin "22") (pinfunction "XTAL1_22") (pintype "passive"))
      (node (ref "Y1") (pin "1") (pinfunction "OSC1_1") (pintype "passive"))
    )
    (net (code "118") (name "/XTAL2") (class "Default")
      (node (ref "C31") (pin "2") (pinfunction "2_2") (pintype "passive"))
      (node (ref "U1") (pin "23") (pinfunction "XTAL2_23") (pintype "passive"))
      (node (ref "Y1") (pin "2") (pinfunction "OSC2_2") (pintype "passive"))
    )
    (net (code "119") (name "/res_but") (class "Default")
      (node (ref "D2") (pin "2") (pinfunction "K_2") (pintype "passive"))
      (node (ref "JP2") (pin "3") (pinfunction "3_3") (pintype "passive"))
      (node (ref "JP8") (pin "3") (pinfunction "3_3") (pintype "passive"))
    )
    (net (code "120") (name "GND") (class "Default")
      (node (ref "C15") (pin "1") (pinfunction "1_1") (pintype "passive"))
      (node (ref "C16") (pin "1") (pinfunction "1_1") (pintype "passive"))
      (node (ref "C17") (pin "1") (pinfunction "1_1") (pintype "passive"))
      (node (ref "C19") (pin "2") (pinfunction "2_2") (pintype "passive"))
      (node (ref "C21") (pin "1") (pinfunction "1_1") (pintype "passive"))
      (node (ref "C22") (pin "1") (pinfunction "1_1") (pintype "passive"))
      (node (ref "C23") (pin "2") (pinfunction "2_2") (pintype "passive"))
      (node (ref "C24") (pin "1") (pinfunction "1_1") (pintype "passive"))
      (node (ref "C25") (pin "1") (pinfunction "1_1") (pintype "passive"))
      (node (ref "C31") (pin "1") (pinfunction "1_1") (pintype "passive"))
      (node (ref "C33") (pin "1") (pinfunction "1_1") (pintype "passive"))
      (node (ref "C34") (pin "2") (pinfunction "2_2") (pintype "passive"))
      (node (ref "C35") (pin "2") (pinfunction "2_2") (pintype "passive"))
      (node (ref "C37") (pin "1") (pinfunction "1_1") (pintype "passive"))
      (node (ref "C38") (pin "1") (pinfunction "1_1") (pintype "passive"))
      (node (ref "C39") (pin "1") (pinfunction "1_1") (pintype "passive"))
      (node (ref "C40") (pin "1") (pinfunction "1_1") (pintype "passive"))
      (node (ref "C41") (pin "1") (pinfunction "1_1") (pintype "passive"))
      (node (ref "J1") (pin "7") (pinfunction "GND_7") (pintype "passive"))
      (node (ref "JP1") (pin "11") (pinfunction "11_11") (pintype "passive"))
      (node (ref "JP1") (pin "12") (pinfunction "12_12") (pintype "passive"))
      (node (ref "JP1") (pin "13") (pinfunction "13_13") (pintype "passive"))
      (node (ref "JP1") (pin "14") (pinfunction "14_14") (pintype "passive"))
      (node (ref "JP1") (pin "59") (pinfunction "59_59") (pintype "passive"))
      (node (ref "JP1") (pin "60") (pinfunction "60_60") (pintype "passive"))
      (node (ref "JP1") (pin "61") (pinfunction "61_61") (pintype "passive"))
      (node (ref "JP1") (pin "62") (pinfunction "62_62") (pintype "passive"))
      (node (ref "JP2") (pin "1") (pinfunction "1_1") (pintype "passive"))
      (node (ref "JP2") (pin "2") (pinfunction "2_2") (pintype "passive"))
      (node (ref "JP4") (pin "20") (pinfunction "20_20") (pintype "passive"))
      (node (ref "Q1") (pin "2") (pinfunction "E_2") (pintype "passive"))
      (node (ref "Q6") (pin "2") (pinfunction "E_2") (pintype "passive"))
      (node (ref "R36") (pin "1") (pinfunction "1_1") (pintype "passive"))
      (node (ref "R57") (pin "1") (pinfunction "1_1") (pintype "passive"))
      (node (ref "R58") (pin "1") (pinfunction "1_1") (pintype "passive"))
      (node (ref "R60") (pin "1") (pinfunction "1_1") (pintype "passive"))
      (node (ref "U1") (pin "11") (pinfunction "Vssa_11") (pintype "passive"))
      (node (ref "U1") (pin "15") (pinfunction "Vss_15") (pintype "passive"))
      (node (ref "U1") (pin "31") (pinfunction "Vss_31") (pintype "passive"))
      (node (ref "U1") (pin "41") (pinfunction "Vss_41") (pintype "passive"))
      (node (ref "U1") (pin "55") (pinfunction "Vss_55") (pintype "passive"))
      (node (ref "U1") (pin "72") (pinfunction "Vss_72") (pintype "passive"))
      (node (ref "U1") (pin "83") (pinfunction "Vss_83") (pintype "passive"))
      (node (ref "U1") (pin "97") (pinfunction "Vss_97") (pintype "passive"))
      (node (ref "U12") (pin "2") (pinfunction "GND_2") (pintype "passive"))
      (node (ref "U12") (pin "8") (pinfunction "S_8") (pintype "passive"))
      (node (ref "U13") (pin "2") (pinfunction "GND_2") (pintype "power_in"))
      (node (ref "U19") (pin "2") (pinfunction "GND_2") (pintype "power_in"))
      (node (ref "U7") (pin "3") (pinfunction "GND_3") (pintype "passive"))
    )
    (net (code "121") (name "Net-(A1-Pad2)") (class "Default")
      (node (ref "A1") (pin "2") (pinfunction "2_2") (pintype "passive"))
      (node (ref "C19") (pin "1") (pinfunction "1_1") (pintype "passive"))
      (node (ref "R56") (pin "1") (pinfunction "1_1") (pintype "passive"))
      (node (ref "R57") (pin "2") (pinfunction "2_2") (pintype "passive"))
    )
    (net (code "122") (name "Net-(C22-Pad2)") (class "Default")
      (node (ref "C22") (pin "2") (pinfunction "2_2") (pintype "passive"))
      (node (ref "K1") (pin "1") (pinfunction "1_1") (pintype "passive"))
      (node (ref "R61") (pin "1") (pinfunction "1_1") (pintype "passive"))
      (node (ref "R64") (pin "1") (pinfunction "1_1") (pintype "passive"))
    )
    (net (code "123") (name "Net-(C23-Pad1)") (class "Default")
      (node (ref "C23") (pin "1") (pinfunction "1_1") (pintype "passive"))
      (node (ref "K1") (pin "3") (pinfunction "3_3") (pintype "passive"))
      (node (ref "R63") (pin "1") (pinfunction "1_1") (pintype "passive"))
      (node (ref "R65") (pin "1") (pinfunction "1_1") (pintype "passive"))
    )
    (net (code "124") (name "Net-(Q1-B)") (class "Default")
      (node (ref "Q1") (pin "1") (pinfunction "B_1") (pintype "passive"))
      (node (ref "R34") (pin "2") (pinfunction "2_2") (pintype "passive"))
      (node (ref "R36") (pin "2") (pinfunction "2_2") (pintype "passive"))
    )
    (net (code "125") (name "Net-(Q1-C)") (class "Default")
      (node (ref "A1") (pin "1") (pinfunction "1_1") (pintype "passive"))
      (node (ref "Q1") (pin "3") (pinfunction "C_3") (pintype "passive"))
    )
    (net (code "126") (name "Net-(Q5-G)") (class "Default")
      (node (ref "JP8") (pin "1") (pinfunction "1_1") (pintype "passive"))
      (node (ref "JP8") (pin "2") (pinfunction "2_2") (pintype "passive"))
      (node (ref "Q5") (pin "1") (pinfunction "G_1") (pintype "passive"))
      (node (ref "U13") (pin "1") (pinfunction "~{RST}_1") (pintype "power_in"))
    )
    (net (code "127") (name "Net-(Q5-S)") (class "Default")
      (node (ref "Q5") (pin "2") (pinfunction "S_2") (pintype "passive"))
      (node (ref "U13") (pin "4") (pinfunction "WDI_4") (pintype "passive"))
    )
    (net (code "128") (name "Net-(Q6-B)") (class "Default")
      (node (ref "Q6") (pin "1") (pinfunction "B_1") (pintype "passive"))
      (node (ref "R35") (pin "2") (pinfunction "2_2") (pintype "passive"))
      (node (ref "R58") (pin "2") (pinfunction "2_2") (pintype "passive"))
    )
    (net (code "129") (name "Net-(Q6-C)") (class "Default")
      (node (ref "K1") (pin "5") (pinfunction "5_5") (pintype "passive"))
      (node (ref "Q6") (pin "3") (pinfunction "C_3") (pintype "passive"))
    )
    (net (code "130") (name "Net-(U7-outA)") (class "Default")
      (node (ref "R40") (pin "2") (pinfunction "2_2") (pintype "passive"))
      (node (ref "U7") (pin "7") (pinfunction "outA_7") (pintype "passive"))
    )
    (net (code "131") (name "Net-(U7-outB)") (class "Default")
      (node (ref "R41") (pin "2") (pinfunction "2_2") (pintype "passive"))
      (node (ref "U7") (pin "5") (pinfunction "outB_5") (pintype "passive"))
    )
    (net (code "132") (name "Net-(U9-IN+)") (class "Default")
      (node (ref "C35") (pin "1") (pinfunction "1_1") (pintype "passive"))
      (node (ref "R60") (pin "2") (pinfunction "2_2") (pintype "passive"))
      (node (ref "R65") (pin "2") (pinfunction "2_2") (pintype "passive"))
      (node (ref "U9") (pin "3") (pinfunction "IN+_3") (pintype "input"))
    )
    (net (code "133") (name "Net-(U9-IN-)") (class "Default")
      (node (ref "C32") (pin "1") (pinfunction "1_1") (pintype "passive"))
      (node (ref "R59") (pin "2") (pinfunction "2_2") (pintype "passive"))
      (node (ref "R64") (pin "2") (pinfunction "2_2") (pintype "passive"))
      (node (ref "U9") (pin "2") (pinfunction "IN-_2") (pintype "input"))
    )
    (net (code "134") (name "Net-(U9-OUT)") (class "Default")
      (node (ref "C24") (pin "2") (pinfunction "2_2") (pintype "passive"))
      (node (ref "C32") (pin "2") (pinfunction "2_2") (pintype "passive"))
      (node (ref "R59") (pin "1") (pinfunction "1_1") (pintype "passive"))
      (node (ref "R66") (pin "1") (pinfunction "1_1") (pintype "passive"))
      (node (ref "U9") (pin "6") (pinfunction "OUT_6") (pintype "output"))
    )
    (net (code "135") (name "unconnected-(JP1-Pad3)") (class "Default")
      (node (ref "JP1") (pin "3") (pinfunction "3_3") (pintype "passive"))
    )
    (net (code "136") (name "unconnected-(JP1-Pad4)") (class "Default")
      (node (ref "JP1") (pin "4") (pinfunction "4_4") (pintype "passive"))
    )
    (net (code "137") (name "unconnected-(JP1-Pad15)") (class "Default")
      (node (ref "JP1") (pin "15") (pinfunction "15_15") (pintype "passive"))
    )
    (net (code "138") (name "unconnected-(JP1-Pad16)") (class "Default")
      (node (ref "JP1") (pin "16") (pinfunction "16_16") (pintype "passive"))
    )
    (net (code "139") (name "unconnected-(JP1-Pad29)") (class "Default")
      (node (ref "JP1") (pin "29") (pinfunction "29_29") (pintype "passive"))
    )
    (net (code "140") (name "unconnected-(JP1-Pad30)") (class "Default")
      (node (ref "JP1") (pin "30") (pinfunction "30_30") (pintype "passive"))
    )
    (net (code "141") (name "unconnected-(JP1-Pad31)") (class "Default")
      (node (ref "JP1") (pin "31") (pinfunction "31_31") (pintype "passive"))
    )
    (net (code "142") (name "unconnected-(JP1-Pad32)") (class "Default")
      (node (ref "JP1") (pin "32") (pinfunction "32_32") (pintype "passive"))
    )
    (net (code "143") (name "unconnected-(JP1-Pad42)") (class "Default")
      (node (ref "JP1") (pin "42") (pinfunction "42_42") (pintype "passive"))
    )
    (net (code "144") (name "unconnected-(JP4-Pad13)") (class "Default")
      (node (ref "JP4") (pin "13") (pinfunction "13_13") (pintype "passive"))
    )
    (net (code "145") (name "unconnected-(JP4-Pad14)") (class "Default")
      (node (ref "JP4") (pin "14") (pinfunction "14_14") (pintype "passive"))
    )
    (net (code "146") (name "unconnected-(JP4-Pad15)") (class "Default")
      (node (ref "JP4") (pin "15") (pinfunction "15_15") (pintype "passive"))
    )
    (net (code "147") (name "unconnected-(JP4-Pad16)") (class "Default")
      (node (ref "JP4") (pin "16") (pinfunction "16_16") (pintype "passive"))
    )
    (net (code "148") (name "unconnected-(JP4-Pad17)") (class "Default")
      (node (ref "JP4") (pin "17") (pinfunction "17_17") (pintype "passive"))
    )
    (net (code "149") (name "unconnected-(K1-Pad2)") (class "Default")
      (node (ref "K1") (pin "2") (pinfunction "2_2") (pintype "passive"))
    )
    (net (code "150") (name "unconnected-(U1-RTCK-Pad100)") (class "Default")
      (node (ref "U1") (pin "100") (pinfunction "RTCK_100") (pintype "passive"))
    )
    (net (code "151") (name "unconnected-(U1-TCK-Pad5)") (class "Default")
      (node (ref "U1") (pin "5") (pinfunction "TCK_5") (pintype "passive"))
    )
    (net (code "152") (name "unconnected-(U1-TDI-Pad2)") (class "Default")
      (node (ref "U1") (pin "2") (pinfunction "TDI_2") (pintype "passive"))
    )
    (net (code "153") (name "unconnected-(U1-TDO-Pad1)") (class "Default")
      (node (ref "U1") (pin "1") (pinfunction "TDO_1") (pintype "passive"))
    )
    (net (code "154") (name "unconnected-(U1-TMS-Pad3)") (class "Default")
      (node (ref "U1") (pin "3") (pinfunction "TMS_3") (pintype "passive"))
    )
    (net (code "155") (name "unconnected-(U1-~{RSTOUT}-Pad14)") (class "Default")
      (node (ref "U1") (pin "14") (pinfunction "~{RSTOUT}_14") (pintype "passive"))
    )
    (net (code "156") (name "unconnected-(U1-~{TRST}-Pad4)") (class "Default")
      (node (ref "U1") (pin "4") (pinfunction "~{TRST}_4") (pintype "passive"))
    )
    (net (code "157") (name "unconnected-(U9-NC-Pad5)") (class "Default")
      (node (ref "U9") (pin "5") (pinfunction "NC_5") (pintype "passive"))
    )
    (net (code "158") (name "unconnected-(U9-VOSTRIM-Pad1)") (class "Default")
      (node (ref "U9") (pin "1") (pinfunction "VOSTRIM_1") (pintype "passive"))
    )
    (net (code "159") (name "unconnected-(U9-VOSTRIM-Pad8)") (class "Default")
      (node (ref "U9") (pin "8") (pinfunction "VOSTRIM_8") (pintype "passive"))
    )
    (net (code "160") (name "unconnected-(U12-Vref-Pad5)") (class "Default")
      (node (ref "U12") (pin "5") (pinfunction "Vref_5") (pintype "passive"))
    )
    (net (code "161") (name "unconnected-(U13-~{MR}-Pad3)") (class "Default")
      (node (ref "U13") (pin "3") (pinfunction "~{MR}_3") (pintype "input"))
    )
    (net (code "162") (name "unconnected-(U19-NC-Pad4)") (class "Default")
      (node (ref "U19") (pin "4") (pinfunction "NC_4") (pintype "passive"))
    )
  )
)
